# I2C_switch.net
KiCad netlist of a schematic drawn in Altium Designer
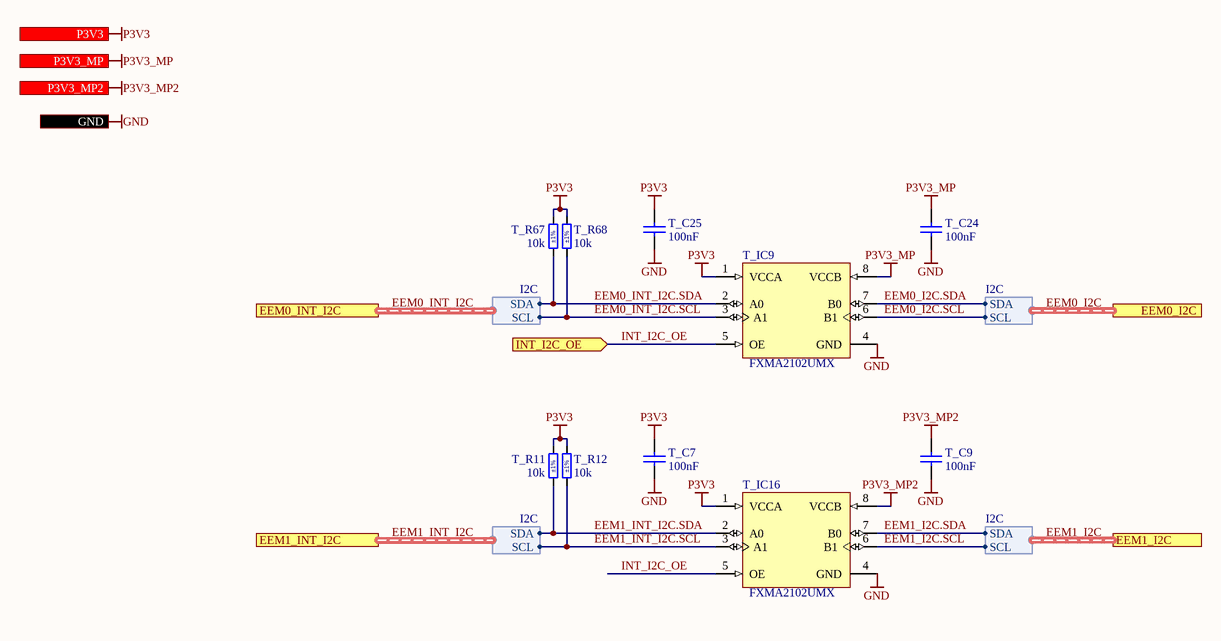
[diagram p0: I2C_switch.SchDoc]

(export (version "E")
  (design (tool "Eeschema 10.0.6"))
  (components
    (comp (ref "T_C7")
      (value "100nF")
      (footprint "CAPC1005X55N")
      (description "Non-polarised capacitor")
      (fields
        (field (name "PART NUMBER") "CC0402_100NF_16V_10%_X5R")
        (field (name "VOLTAGE") "16V")
        (field (name "AUTHOR") "CERN DEM JLC")
      )
      (libsource (lib "Capacitors") (part "Capacitor - non polarized"))
    )
    (comp (ref "T_C9")
      (value "100nF")
      (footprint "CAPC1005X55N")
      (description "Non-polarised capacitor")
      (fields
        (field (name "PART NUMBER") "CC0402_100NF_16V_10%_X5R")
        (field (name "VOLTAGE") "16V")
        (field (name "AUTHOR") "CERN DEM JLC")
      )
      (libsource (lib "Capacitors") (part "Capacitor - non polarized"))
    )
    (comp (ref "T_C24")
      (value "100nF")
      (footprint "CAPC1005X55N")
      (description "Non-polarised capacitor")
      (fields
        (field (name "PART NUMBER") "CC0402_100NF_16V_10%_X5R")
        (field (name "VOLTAGE") "16V")
        (field (name "AUTHOR") "CERN DEM JLC")
      )
      (libsource (lib "Capacitors") (part "Capacitor - non polarized"))
    )
    (comp (ref "T_C25")
      (value "100nF")
      (footprint "CAPC1005X55N")
      (description "Non-polarised capacitor")
      (fields
        (field (name "PART NUMBER") "CC0402_100NF_16V_10%_X5R")
        (field (name "VOLTAGE") "16V")
        (field (name "AUTHOR") "CERN DEM JLC")
      )
      (libsource (lib "Capacitors") (part "Capacitor - non polarized"))
    )
    (comp (ref "T_IC9")
      (value "FXMA2102UMX")
      (footprint "FXMA2102UMX")
      (description "Dual Supply 2-Bit Voltage Translator/Buffer/Repeater Isolator for I2C Applications")
      (fields (field (name "MANUFACTURER") "Onsemi"))
      (libsource (lib "TechnoSystem Workspace") (part "FXMA2102UMX"))
    )
    (comp (ref "T_IC16")
      (value "FXMA2102UMX")
      (footprint "FXMA2102UMX")
      (description "Dual Supply 2-Bit Voltage Translator/Buffer/Repeater Isolator for I2C Applications")
      (fields (field (name "MANUFACTURER") "Onsemi"))
      (libsource (lib "TechnoSystem Workspace") (part "FXMA2102UMX"))
    )
    (comp (ref "T_R11")
      (value "10k")
      (footprint "RESC1005X40N")
      (description "Resistor - 1%")
      (fields
        (field (name "TOLERANCE") "±1%")
        (field (name "PART NUMBER") "R0402_10K_1%_0.0625W_100PPM")
        (field (name "POWER") "0.0625W")
        (field (name "AUTHOR") "CERN DEM JLC")
      )
      (libsource (lib "Resistors") (part "Resistor - 1%"))
    )
    (comp (ref "T_R12")
      (value "10k")
      (footprint "RESC1005X40N")
      (description "Resistor - 1%")
      (fields
        (field (name "TOLERANCE") "±1%")
        (field (name "PART NUMBER") "R0402_10K_1%_0.0625W_100PPM")
        (field (name "POWER") "0.0625W")
        (field (name "AUTHOR") "CERN DEM JLC")
      )
      (libsource (lib "Resistors") (part "Resistor - 1%"))
    )
    (comp (ref "T_R67")
      (value "10k")
      (footprint "RESC1005X40N")
      (description "Resistor - 1%")
      (fields
        (field (name "TOLERANCE") "±1%")
        (field (name "PART NUMBER") "R0402_10K_1%_0.0625W_100PPM")
        (field (name "POWER") "0.0625W")
        (field (name "AUTHOR") "CERN DEM JLC")
      )
      (libsource (lib "Resistors") (part "Resistor - 1%"))
    )
    (comp (ref "T_R68")
      (value "10k")
      (footprint "RESC1005X40N")
      (description "Resistor - 1%")
      (fields
        (field (name "TOLERANCE") "±1%")
        (field (name "PART NUMBER") "R0402_10K_1%_0.0625W_100PPM")
        (field (name "POWER") "0.0625W")
        (field (name "AUTHOR") "CERN DEM JLC")
      )
      (libsource (lib "Resistors") (part "Resistor - 1%"))
    )
  )
  (nets
    (net (code "5") (name "/EEM0_I2C.SCL") (class "Default")
      (node (ref "T_IC9") (pin "6") (pinfunction "B1_6") (pintype "bidirectional"))
    )
    (net (code "6") (name "/EEM0_I2C.SDA") (class "Default")
      (node (ref "T_IC9") (pin "7") (pinfunction "B0_7") (pintype "bidirectional"))
    )
    (net (code "8") (name "/EEM0_INT_I2C.SCL") (class "Default")
      (node (ref "T_IC9") (pin "3") (pinfunction "A1_3") (pintype "bidirectional"))
      (node (ref "T_R68") (pin "1") (pinfunction "1_1") (pintype "passive"))
    )
    (net (code "9") (name "/EEM0_INT_I2C.SDA") (class "Default")
      (node (ref "T_IC9") (pin "2") (pinfunction "A0_2") (pintype "bidirectional"))
      (node (ref "T_R67") (pin "1") (pinfunction "1_1") (pintype "passive"))
    )
    (net (code "11") (name "/EEM1_I2C.SCL") (class "Default")
      (node (ref "T_IC16") (pin "6") (pinfunction "B1_6") (pintype "bidirectional"))
    )
    (net (code "12") (name "/EEM1_I2C.SDA") (class "Default")
      (node (ref "T_IC16") (pin "7") (pinfunction "B0_7") (pintype "bidirectional"))
    )
    (net (code "14") (name "/EEM1_INT_I2C.SCL") (class "Default")
      (node (ref "T_IC16") (pin "3") (pinfunction "A1_3") (pintype "bidirectional"))
      (node (ref "T_R12") (pin "1") (pinfunction "1_1") (pintype "passive"))
    )
    (net (code "15") (name "/EEM1_INT_I2C.SDA") (class "Default")
      (node (ref "T_IC16") (pin "2") (pinfunction "A0_2") (pintype "bidirectional"))
      (node (ref "T_R11") (pin "1") (pinfunction "1_1") (pintype "passive"))
    )
    (net (code "17") (name "/INT_I2C_OE") (class "Default")
      (node (ref "T_IC16") (pin "5") (pinfunction "OE_5") (pintype "input"))
      (node (ref "T_IC9") (pin "5") (pinfunction "OE_5") (pintype "input"))
    )
    (net (code "18") (name "GND") (class "Default")
      (node (ref "T_C24") (pin "1") (pinfunction "1_1") (pintype "passive"))
      (node (ref "T_C25") (pin "1") (pinfunction "1_1") (pintype "passive"))
      (node (ref "T_C7") (pin "1") (pinfunction "1_1") (pintype "passive"))
      (node (ref "T_C9") (pin "1") (pinfunction "1_1") (pintype "passive"))
      (node (ref "T_IC16") (pin "4") (pinfunction "GND_4") (pintype "power_in"))
      (node (ref "T_IC9") (pin "4") (pinfunction "GND_4") (pintype "power_in"))
    )
    (net (code "19") (name "P3V3") (class "Default")
      (node (ref "T_C25") (pin "2") (pinfunction "2_2") (pintype "passive"))
      (node (ref "T_C7") (pin "2") (pinfunction "2_2") (pintype "passive"))
      (node (ref "T_IC16") (pin "1") (pinfunction "VCCA_1") (pintype "input"))
      (node (ref "T_IC9") (pin "1") (pinfunction "VCCA_1") (pintype "input"))
      (node (ref "T_R11") (pin "2") (pinfunction "2_2") (pintype "passive"))
      (node (ref "T_R12") (pin "2") (pinfunction "2_2") (pintype "passive"))
      (node (ref "T_R67") (pin "2") (pinfunction "2_2") (pintype "passive"))
      (node (ref "T_R68") (pin "2") (pinfunction "2_2") (pintype "passive"))
    )
    (net (code "20") (name "P3V3_MP") (class "Default")
      (node (ref "T_C24") (pin "2") (pinfunction "2_2") (pintype "passive"))
      (node (ref "T_IC9") (pin "8") (pinfunction "VCCB_8") (pintype "input"))
    )
    (net (code "21") (name "P3V3_MP2") (class "Default")
      (node (ref "T_C9") (pin "2") (pinfunction "2_2") (pintype "passive"))
      (node (ref "T_IC16") (pin "8") (pinfunction "VCCB_8") (pintype "input"))
    )
  )
)
